# esp-01_lite2.net
KiCad netlist of a schematic drawn in EAGLE
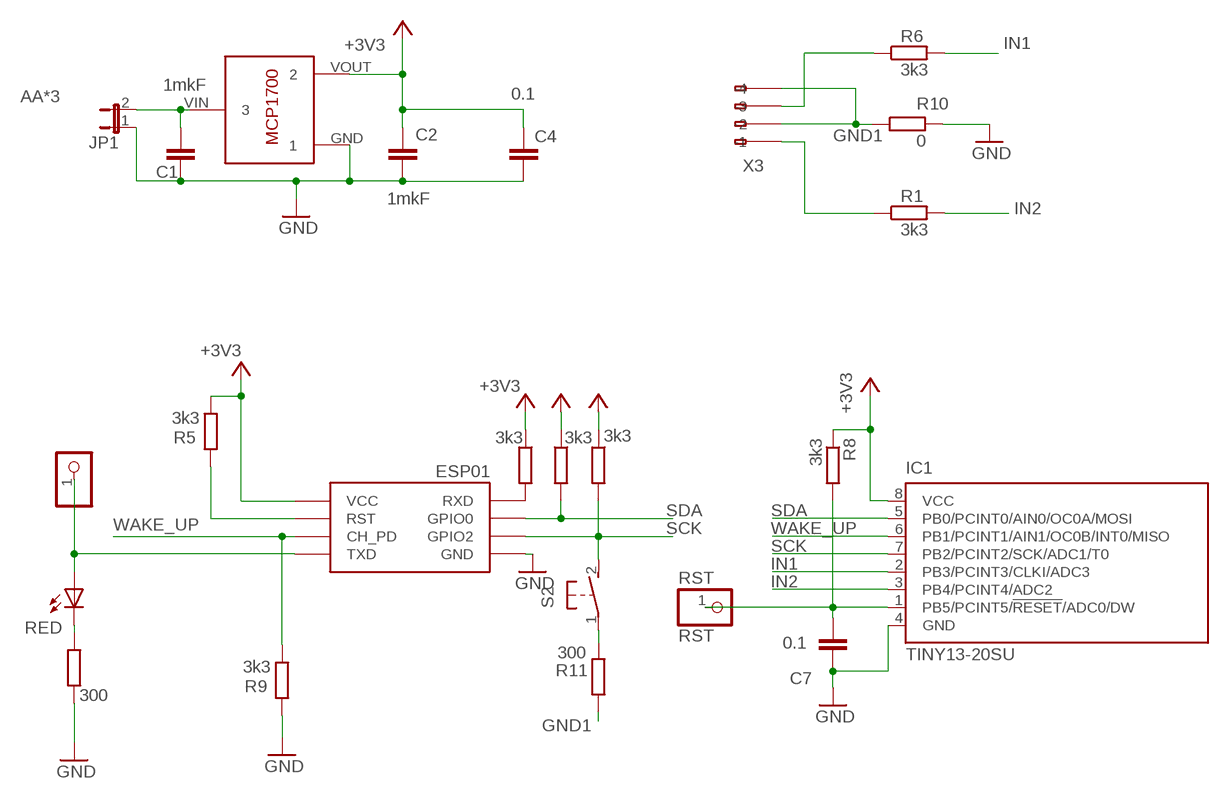
[diagram p0: schematic, sheet 1]

(export (version "E")
  (design (tool "Eeschema 10.0.6"))
  (components
    (comp (ref "C1")
      (value "1mkF")
      (footprint "eagle-import:C0805")
      (libsource (lib "eagle-import") (part "resistor_348_C-EUC0805"))
    )
    (comp (ref "C2")
      (value "1mkF")
      (footprint "eagle-import:C0805")
      (libsource (lib "eagle-import") (part "resistor_348_C-EUC0805"))
    )
    (comp (ref "C4")
      (value "0.1")
      (footprint "eagle-import:C0805")
      (libsource (lib "eagle-import") (part "C-EUC0805"))
    )
    (comp (ref "C7")
      (value "0.1")
      (footprint "eagle-import:C0805")
      (libsource (lib "eagle-import") (part "resistor_348_C-EUC0805"))
    )
    (comp (ref "IC1")
      (value "TINY13-20SU")
      (footprint "eagle-import:8S2")
      (fields (field (name "MPN") "ATTINY13-20SU"))
      (libsource (lib "eagle-import") (part "TINY13SU-20"))
    )
    (comp (ref "JP1")
      (value "JP1E")
      (footprint "eagle-import:JP1")
      (libsource (lib "eagle-import") (part "JP1E"))
    )
    (comp (ref "LED1")
      (value "RED")
      (footprint "eagle-import:SML0805")
      (libsource (lib "eagle-import") (part "LEDSML0805"))
    )
    (comp (ref "LOG")
      (value "LOG")
      (footprint "eagle-import:1X01")
      (libsource (lib "eagle-import") (part "PINHD-1X1"))
    )
    (comp (ref "R1")
      (value "3k3")
      (footprint "eagle-import:M0805")
      (fields (field (name "SPICEPREFIX") "R"))
      (libsource (lib "eagle-import") (part "resistor_348_R-EU_M0805"))
    )
    (comp (ref "R2")
      (value "3k3")
      (footprint "eagle-import:R0805")
      (fields (field (name "OM") "3k6"))
      (libsource (lib "eagle-import") (part "R-EU_R0805"))
    )
    (comp (ref "R3")
      (value "3k3")
      (footprint "eagle-import:R0805")
      (fields (field (name "OM") "3k6"))
      (libsource (lib "eagle-import") (part "rcl_334_R-EU_R0805"))
    )
    (comp (ref "R4")
      (value "300")
      (footprint "eagle-import:0207_2V")
      (fields (field (name "OM") "200"))
      (libsource (lib "eagle-import") (part "rcl_334_R-EU_0207/2V"))
    )
    (comp (ref "R5")
      (value "3k3")
      (footprint "eagle-import:R0805")
      (fields (field (name "OM") "3k6"))
      (libsource (lib "eagle-import") (part "R-EU_R0805"))
    )
    (comp (ref "R6")
      (value "3k3")
      (footprint "eagle-import:M0805")
      (libsource (lib "eagle-import") (part "resistor_348_R-EU_M0805"))
    )
    (comp (ref "R7")
      (value "3k3")
      (footprint "eagle-import:R0805")
      (fields (field (name "OM") "3k6"))
      (libsource (lib "eagle-import") (part "R-EU_R0805"))
    )
    (comp (ref "R8")
      (value "3k3")
      (footprint "eagle-import:R0805")
      (fields (field (name "OM") "3k6"))
      (libsource (lib "eagle-import") (part "rcl_334_R-EU_R0805"))
    )
    (comp (ref "R9")
      (value "3k3")
      (footprint "eagle-import:R0805")
      (fields (field (name "OM") "3k6"))
      (libsource (lib "eagle-import") (part "R-EU_R0805"))
    )
    (comp (ref "R10")
      (value "0")
      (footprint "eagle-import:M0805")
      (libsource (lib "eagle-import") (part "resistor_348_R-EU_M0805"))
    )
    (comp (ref "R11")
      (value "300")
      (footprint "eagle-import:R0805")
      (fields (field (name "OM") "3k6"))
      (libsource (lib "eagle-import") (part "R-EU_R0805"))
    )
    (comp (ref "RST")
      (value "RST")
      (footprint "eagle-import:1X01")
      (libsource (lib "eagle-import") (part "PINHD-1X1"))
    )
    (comp (ref "S2")
      (value "31-XX")
      (footprint "eagle-import:B3F-31XX")
      (fields (field (name "MPN") "B3F-3100"))
      (libsource (lib "eagle-import") (part "31-XX"))
    )
    (comp (ref "U$1")
      (value "ESP01")
      (footprint "eagle-import:ESP01")
      (libsource (lib "eagle-import") (part "ESP01"))
    )
    (comp (ref "U$2")
      (value "MCP1700T-3302E/TT")
      (footprint "eagle-import:MCP1700T-3302E_TT")
      (libsource (lib "eagle-import") (part "MCP1700T-3302E/TT"))
    )
    (comp (ref "X3")
      (value "233-104")
      (footprint "eagle-import:233-104")
      (libsource (lib "eagle-import") (part "233-104"))
    )
  )
  (nets
    (net (code "1") (name "+3V3") (class "Default")
      (node (ref "C2") (pin "1") (pinfunction "1_1") (pintype "passive"))
      (node (ref "C4") (pin "1") (pinfunction "1_1") (pintype "passive"))
      (node (ref "IC1") (pin "8") (pinfunction "VCC_8") (pintype "power_in"))
      (node (ref "R2") (pin "1") (pinfunction "1_1") (pintype "passive"))
      (node (ref "R3") (pin "1") (pinfunction "1_1") (pintype "passive"))
      (node (ref "R5") (pin "1") (pinfunction "1_1") (pintype "passive"))
      (node (ref "R7") (pin "1") (pinfunction "1_1") (pintype "passive"))
      (node (ref "R8") (pin "1") (pinfunction "1_1") (pintype "passive"))
      (node (ref "U$1") (pin "VCC") (pinfunction "VCC_VCC") (pintype "bidirectional"))
      (node (ref "U$2") (pin "VOUT") (pinfunction "2_VOUT") (pintype "bidirectional"))
    )
    (net (code "2") (name "/AA*3") (class "Default")
      (node (ref "C1") (pin "1") (pinfunction "1_1") (pintype "passive"))
      (node (ref "JP1") (pin "2") (pinfunction "2_2") (pintype "passive"))
      (node (ref "U$2") (pin "VIN") (pinfunction "3_VIN") (pintype "bidirectional"))
    )
    (net (code "3") (name "/GND1") (class "Default")
      (node (ref "R10") (pin "1") (pinfunction "1_1") (pintype "passive"))
      (node (ref "R11") (pin "2") (pinfunction "2_2") (pintype "passive"))
      (node (ref "X3") (pin "A2") (pinfunction "-2_A2") (pintype "passive"))
      (node (ref "X3") (pin "A4") (pinfunction "-4_A4") (pintype "passive"))
    )
    (net (code "4") (name "/IN1") (class "Default")
      (node (ref "IC1") (pin "2") (pinfunction "PB3/PCINT3/CLKI/ADC3_2") (pintype "bidirectional"))
      (node (ref "R6") (pin "2") (pinfunction "2_2") (pintype "passive"))
    )
    (net (code "5") (name "/IN2") (class "Default")
      (node (ref "IC1") (pin "3") (pinfunction "PB4/PCINT4/ADC2_3") (pintype "bidirectional"))
      (node (ref "R1") (pin "2") (pinfunction "2_2") (pintype "passive"))
    )
    (net (code "6") (name "/SCK") (class "Default")
      (node (ref "IC1") (pin "7") (pinfunction "PB2/PCINT2/SCK/ADC1/T0_7") (pintype "bidirectional"))
      (node (ref "R2") (pin "2") (pinfunction "2_2") (pintype "passive"))
      (node (ref "S2") (pin "2") (pinfunction "S_2") (pintype "passive"))
      (node (ref "U$1") (pin "GPIO2") (pinfunction "GPIO2_GPIO2") (pintype "bidirectional"))
    )
    (net (code "7") (name "/SDA") (class "Default")
      (node (ref "IC1") (pin "5") (pinfunction "PB0/PCINT0/AIN0/OC0A/MOSI_5") (pintype "bidirectional"))
      (node (ref "R3") (pin "2") (pinfunction "2_2") (pintype "passive"))
      (node (ref "U$1") (pin "GPIO0") (pinfunction "GPIO0_GPIO0") (pintype "bidirectional"))
    )
    (net (code "8") (name "/WAKE_UP") (class "Default")
      (node (ref "IC1") (pin "6") (pinfunction "PB1/PCINT1/AIN1/OC0B/INT0/MISO_6") (pintype "bidirectional"))
      (node (ref "R9") (pin "1") (pinfunction "1_1") (pintype "passive"))
      (node (ref "U$1") (pin "CH_PD") (pinfunction "CH_PD_CH_PD") (pintype "bidirectional"))
    )
    (net (code "9") (name "GND") (class "Default")
      (node (ref "C1") (pin "2") (pinfunction "2_2") (pintype "passive"))
      (node (ref "C2") (pin "2") (pinfunction "2_2") (pintype "passive"))
      (node (ref "C4") (pin "2") (pinfunction "2_2") (pintype "passive"))
      (node (ref "C7") (pin "1") (pinfunction "1_1") (pintype "passive"))
      (node (ref "IC1") (pin "4") (pinfunction "GND_4") (pintype "power_in"))
      (node (ref "JP1") (pin "1") (pinfunction "1_1") (pintype "passive"))
      (node (ref "R10") (pin "2") (pinfunction "2_2") (pintype "passive"))
      (node (ref "R4") (pin "2") (pinfunction "2_2") (pintype "passive"))
      (node (ref "R9") (pin "2") (pinfunction "2_2") (pintype "passive"))
      (node (ref "U$1") (pin "GND") (pinfunction "GND_GND") (pintype "bidirectional"))
      (node (ref "U$2") (pin "GND") (pinfunction "1_GND") (pintype "bidirectional"))
    )
    (net (code "10") (name "Net-(IC1-PB5{slash}PCINT5{slash}~{RESET}{slash}ADC0{slash}DW)") (class "Default")
      (node (ref "C7") (pin "2") (pinfunction "2_2") (pintype "passive"))
      (node (ref "IC1") (pin "1") (pinfunction "PB5/PCINT5/~{RESET}/ADC0/DW_1") (pintype "bidirectional"))
      (node (ref "R8") (pin "2") (pinfunction "2_2") (pintype "passive"))
      (node (ref "RST") (pin "1") (pinfunction "1_1") (pintype "passive"))
    )
    (net (code "11") (name "Net-(LED1-PadC)") (class "Default")
      (node (ref "LED1") (pin "C") (pinfunction "C_C") (pintype "passive"))
      (node (ref "R4") (pin "1") (pinfunction "1_1") (pintype "passive"))
    )
    (net (code "12") (name "Net-(R5-Pad2)") (class "Default")
      (node (ref "R5") (pin "2") (pinfunction "2_2") (pintype "passive"))
      (node (ref "U$1") (pin "RST") (pinfunction "RST_RST") (pintype "bidirectional"))
    )
    (net (code "13") (name "Net-(S2-P)") (class "Default")
      (node (ref "R11") (pin "1") (pinfunction "1_1") (pintype "passive"))
      (node (ref "S2") (pin "1") (pinfunction "P_1") (pintype "passive"))
    )
    (net (code "14") (name "Net-(U$1-RXD)") (class "Default")
      (node (ref "R7") (pin "2") (pinfunction "2_2") (pintype "passive"))
      (node (ref "U$1") (pin "RX") (pinfunction "RXD_RX") (pintype "bidirectional"))
    )
    (net (code "15") (name "Net-(U$1-TXD)") (class "Default")
      (node (ref "LED1") (pin "A") (pinfunction "A_A") (pintype "passive"))
      (node (ref "LOG") (pin "1") (pinfunction "1_1") (pintype "passive"))
      (node (ref "U$1") (pin "TX") (pinfunction "TXD_TX") (pintype "bidirectional"))
    )
    (net (code "16") (name "Net-(X3--1)") (class "Default")
      (node (ref "R1") (pin "1") (pinfunction "1_1") (pintype "passive"))
      (node (ref "X3") (pin "A1") (pinfunction "-1_A1") (pintype "passive"))
    )
    (net (code "17") (name "Net-(X3--3)") (class "Default")
      (node (ref "R6") (pin "1") (pinfunction "1_1") (pintype "passive"))
      (node (ref "X3") (pin "A3") (pinfunction "-3_A3") (pintype "passive"))
    )
    (net (code "18") (name "unconnected-(X3-B-1-PadB1)") (class "Default")
      (node (ref "X3") (pin "B1") (pinfunction "B-1_B1") (pintype "passive"))
    )
    (net (code "19") (name "unconnected-(X3-B-2-PadB2)") (class "Default")
      (node (ref "X3") (pin "B2") (pinfunction "B-2_B2") (pintype "passive"))
    )
    (net (code "20") (name "unconnected-(X3-B-3-PadB3)") (class "Default")
      (node (ref "X3") (pin "B3") (pinfunction "B-3_B3") (pintype "passive"))
    )
    (net (code "21") (name "unconnected-(X3-B-4-PadB4)") (class "Default")
      (node (ref "X3") (pin "B4") (pinfunction "B-4_B4") (pintype "passive"))
    )
  )
)
